# Indicator_Board.net
KiCad netlist of a schematic drawn in Altium Designer
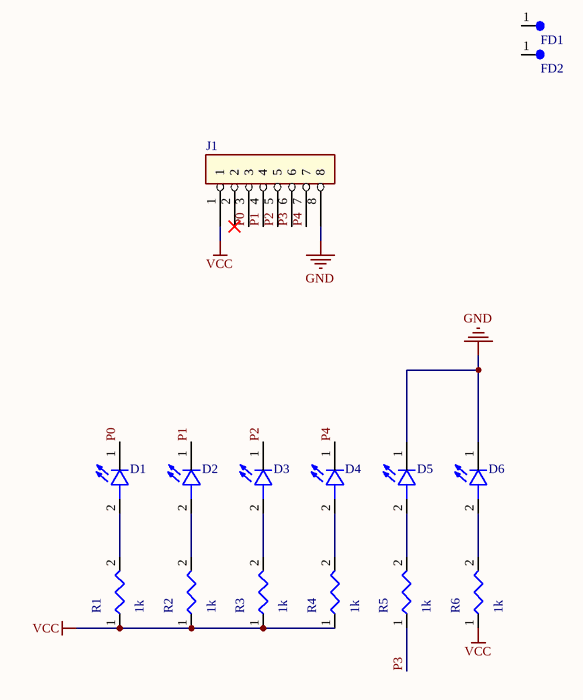
[diagram p0: Indicator_Board.SchDoc]

(export (version "E")
  (design (tool "Eeschema 10.0.6"))
  (components
    (comp (ref "D1")
      (value "APA3010QBC/G-GX")
      (footprint "LED_APA3010QBC/G-GX")
      (description "Surface Mount LED; Size : 3.0X1.0mm ; Color: Blue; Lens: Water Clear")
      (libsource (lib "Indicator_Board") (part "APA3010QBC/G-GX"))
    )
    (comp (ref "D2")
      (value "APA3010QBC/G-GX")
      (footprint "LED_APA3010QBC/G-GX")
      (description "Surface Mount LED; Size : 3.0X1.0mm ; Color: Blue; Lens: Water Clear")
      (libsource (lib "Indicator_Board") (part "APA3010QBC/G-GX"))
    )
    (comp (ref "D3")
      (value "APA3010QBC/G-GX")
      (footprint "LED_APA3010QBC/G-GX")
      (description "Surface Mount LED; Size : 3.0X1.0mm ; Color: Blue; Lens: Water Clear")
      (libsource (lib "Indicator_Board") (part "APA3010QBC/G-GX"))
    )
    (comp (ref "D4")
      (value "APA3010QBC/G-GX")
      (footprint "LED_APA3010QBC/G-GX")
      (description "Surface Mount LED; Size : 3.0X1.0mm ; Color: Blue; Lens: Water Clear")
      (libsource (lib "Indicator_Board") (part "APA3010QBC/G-GX"))
    )
    (comp (ref "D5")
      (value "APA3010QBC/G-GX")
      (footprint "LED_APA3010QBC/G-GX")
      (description "Surface Mount LED; Size : 3.0X1.0mm ; Color: Blue; Lens: Water Clear")
      (libsource (lib "Indicator_Board") (part "APA3010QBC/G-GX"))
    )
    (comp (ref "D6")
      (value "APA3010QBC/G-GX")
      (footprint "LED_APA3010QBC/G-GX")
      (description "Surface Mount LED; Size : 3.0X1.0mm ; Color: Blue; Lens: Water Clear")
      (libsource (lib "Indicator_Board") (part "APA3010QBC/G-GX"))
    )
    (comp (ref "FD1")
      (value "Fiducial")
      (footprint "FD")
      (libsource (lib "Indicator_Board") (part "Fiducial"))
    )
    (comp (ref "FD2")
      (value "Fiducial")
      (footprint "FD")
      (libsource (lib "Indicator_Board") (part "Fiducial"))
    )
    (comp (ref "J1")
      (value "HEADER 8x1")
      (footprint "CONN_8x1")
      (libsource (lib "OOLITEV8") (part "HEADER 8x1"))
    )
    (comp (ref "R1") (value "1k") (footprint "1206-R") (libsource (lib "Indicator_Board") (part "Res")))
    (comp (ref "R2") (value "1k") (footprint "1206-R") (libsource (lib "Indicator_Board") (part "Res")))
    (comp (ref "R3") (value "1k") (footprint "1206-R") (libsource (lib "Indicator_Board") (part "Res")))
    (comp (ref "R4") (value "1k") (footprint "1206-R") (libsource (lib "Indicator_Board") (part "Res")))
    (comp (ref "R5") (value "1k") (footprint "1206-R") (libsource (lib "Indicator_Board") (part "Res")))
    (comp (ref "R6") (value "1k") (footprint "1206-R") (libsource (lib "Indicator_Board") (part "Res")))
  )
  (nets
    (net (code "1") (name "/P0") (class "Default")
      (node (ref "D1") (pin "1") (pinfunction "C_1") (pintype "passive"))
      (node (ref "J1") (pin "3") (pinfunction "3_3") (pintype "passive"))
    )
    (net (code "2") (name "/P1") (class "Default")
      (node (ref "D2") (pin "1") (pinfunction "C_1") (pintype "passive"))
      (node (ref "J1") (pin "4") (pinfunction "4_4") (pintype "passive"))
    )
    (net (code "3") (name "/P2") (class "Default")
      (node (ref "D3") (pin "1") (pinfunction "C_1") (pintype "passive"))
      (node (ref "J1") (pin "5") (pinfunction "5_5") (pintype "passive"))
    )
    (net (code "4") (name "/P3") (class "Default")
      (node (ref "J1") (pin "6") (pinfunction "6_6") (pintype "passive"))
      (node (ref "R5") (pin "1") (pinfunction "1_1") (pintype "passive"))
    )
    (net (code "5") (name "/P4") (class "Default")
      (node (ref "D4") (pin "1") (pinfunction "C_1") (pintype "passive"))
      (node (ref "J1") (pin "7") (pinfunction "7_7") (pintype "passive"))
    )
    (net (code "6") (name "GND") (class "Default")
      (node (ref "D5") (pin "1") (pinfunction "C_1") (pintype "passive"))
      (node (ref "D6") (pin "1") (pinfunction "C_1") (pintype "passive"))
      (node (ref "J1") (pin "8") (pinfunction "8_8") (pintype "passive"))
    )
    (net (code "7") (name "Net-(D1-A)") (class "Default")
      (node (ref "D1") (pin "2") (pinfunction "A_2") (pintype "passive"))
      (node (ref "R1") (pin "2") (pinfunction "2_2") (pintype "passive"))
    )
    (net (code "8") (name "Net-(D2-A)") (class "Default")
      (node (ref "D2") (pin "2") (pinfunction "A_2") (pintype "passive"))
      (node (ref "R2") (pin "2") (pinfunction "2_2") (pintype "passive"))
    )
    (net (code "9") (name "Net-(D3-A)") (class "Default")
      (node (ref "D3") (pin "2") (pinfunction "A_2") (pintype "passive"))
      (node (ref "R3") (pin "2") (pinfunction "2_2") (pintype "passive"))
    )
    (net (code "10") (name "Net-(D4-A)") (class "Default")
      (node (ref "D4") (pin "2") (pinfunction "A_2") (pintype "passive"))
      (node (ref "R4") (pin "2") (pinfunction "2_2") (pintype "passive"))
    )
    (net (code "11") (name "Net-(D5-A)") (class "Default")
      (node (ref "D5") (pin "2") (pinfunction "A_2") (pintype "passive"))
      (node (ref "R5") (pin "2") (pinfunction "2_2") (pintype "passive"))
    )
    (net (code "12") (name "Net-(D6-A)") (class "Default")
      (node (ref "D6") (pin "2") (pinfunction "A_2") (pintype "passive"))
      (node (ref "R6") (pin "2") (pinfunction "2_2") (pintype "passive"))
    )
    (net (code "13") (name "VCC") (class "Default")
      (node (ref "J1") (pin "1") (pinfunction "1_1") (pintype "passive"))
      (node (ref "R1") (pin "1") (pinfunction "1_1") (pintype "passive"))
      (node (ref "R2") (pin "1") (pinfunction "1_1") (pintype "passive"))
      (node (ref "R3") (pin "1") (pinfunction "1_1") (pintype "passive"))
      (node (ref "R4") (pin "1") (pinfunction "1_1") (pintype "passive"))
      (node (ref "R6") (pin "1") (pinfunction "1_1") (pintype "passive"))
    )
    (net (code "14") (name "unconnected-(FD1-Pad1)") (class "Default")
      (node (ref "FD1") (pin "1") (pinfunction "1_1") (pintype "passive"))
    )
    (net (code "15") (name "unconnected-(FD2-Pad1)") (class "Default")
      (node (ref "FD2") (pin "1") (pinfunction "1_1") (pintype "passive"))
    )
    (net (code "16") (name "unconnected-(J1-Pad2)") (class "Default")
      (node (ref "J1") (pin "2") (pinfunction "2_2") (pintype "passive+no_connect"))
    )
  )
)
